# Schematic.net
KiCad netlist of a schematic drawn in Altium Designer
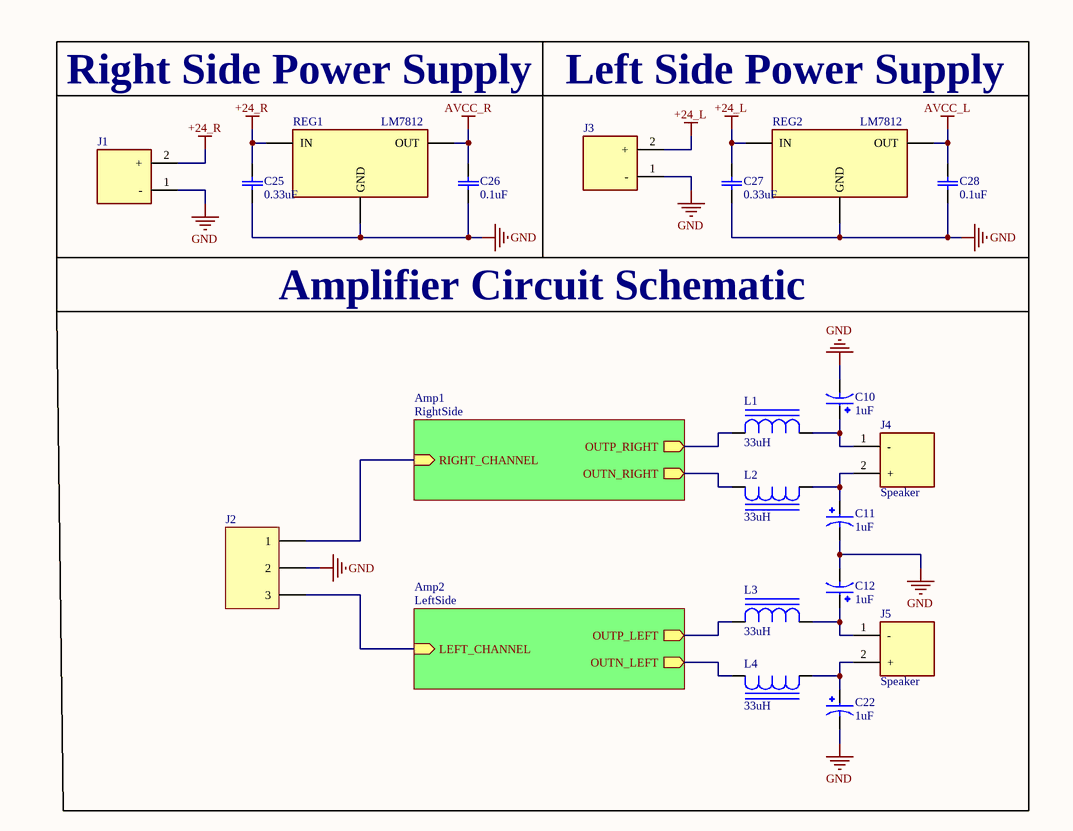
[diagram p0: Schematic.SchDoc]

(export (version "E")
  (design (tool "Eeschema 10.0.6"))
  (components
    (comp (ref "C10")
      (value "1uF")
      (footprint "CAPRADIAL_16X10")
      (fields
        (field (name "DIGI-KEY_PART_NUMBER") "P13679-ND")
        (field (name "MP") "EEU-EE2W560")
        (field (name "MF") "Panasonic")
      )
      (libsource (lib "AltiumLibrary-Mugetsu") (part "CAP ELETRO/TANT"))
    )
    (comp (ref "C11")
      (value "1uF")
      (footprint "CAPRADIAL_16X10")
      (fields
        (field (name "DIGI-KEY_PART_NUMBER") "P13679-ND")
        (field (name "MP") "EEU-EE2W560")
        (field (name "MF") "Panasonic")
      )
      (libsource (lib "") (part "CAP ELETRO/TANT_1"))
    )
    (comp (ref "C12")
      (value "1uF")
      (footprint "CAPRADIAL_16X10")
      (fields
        (field (name "DIGI-KEY_PART_NUMBER") "P13679-ND")
        (field (name "MP") "EEU-EE2W560")
        (field (name "MF") "Panasonic")
      )
      (libsource (lib "AltiumLibrary-Mugetsu") (part "CAP ELETRO/TANT"))
    )
    (comp (ref "C22")
      (value "1uF")
      (footprint "CAPRADIAL_16X10")
      (fields
        (field (name "DIGI-KEY_PART_NUMBER") "P13679-ND")
        (field (name "MP") "EEU-EE2W560")
        (field (name "MF") "Panasonic")
      )
      (libsource (lib "") (part "CAP ELETRO/TANT_1"))
    )
    (comp (ref "C25")
      (value "0.33uF")
      (footprint "CERAMIC0805")
      (fields (field (name "MF") "KEMET") (field (name "MP") "TAJC226M025RNJ"))
      (libsource (lib "AltiumLibrary-Mugetsu") (part "Cap"))
    )
    (comp (ref "C26")
      (value "0.1uF")
      (footprint "CERAMIC0805")
      (fields (field (name "MF") "KEMET") (field (name "MP") "TAJC226M025RNJ"))
      (libsource (lib "AltiumLibrary-Mugetsu") (part "Cap"))
    )
    (comp (ref "C27")
      (value "0.33uF")
      (footprint "CERAMIC0805")
      (fields (field (name "MF") "KEMET") (field (name "MP") "TAJC226M025RNJ"))
      (libsource (lib "AltiumLibrary-Mugetsu") (part "Cap"))
    )
    (comp (ref "C28")
      (value "0.1uF")
      (footprint "CERAMIC0805")
      (fields (field (name "MF") "KEMET") (field (name "MP") "TAJC226M025RNJ"))
      (libsource (lib "AltiumLibrary-Mugetsu") (part "Cap"))
    )
    (comp (ref "J1")
      (value "Borne KF301-2P")
      (footprint "Borne KF301-2P")
      (description "2 Pin Terminal Block 5mm Pitch")
      (fields (field (name "MP") "KF301-2P"))
      (libsource (lib "AltiumLibrary-Mugetsu") (part "Borne KF301-2P"))
    )
    (comp (ref "J2")
      (value "Borne KF301-3P")
      (footprint "Borne KF301-3P")
      (libsource (lib "AltiumLibrary-Mugetsu") (part "Borne KF301-3P"))
    )
    (comp (ref "J3")
      (value "Borne KF301-2P")
      (footprint "Borne KF301-2P")
      (description "2 Pin Terminal Block 5mm Pitch")
      (fields (field (name "MP") "KF301-2P"))
      (libsource (lib "AltiumLibrary-Mugetsu") (part "Borne KF301-2P"))
    )
    (comp (ref "J4")
      (value "Speaker")
      (footprint "Borne KF301-2P")
      (description "2 Pin Terminal Block 5mm Pitch")
      (fields (field (name "MP") "KF301-2P"))
      (libsource (lib "") (part "Borne KF301-2P_1"))
    )
    (comp (ref "J5")
      (value "Speaker")
      (footprint "Borne KF301-2P")
      (description "2 Pin Terminal Block 5mm Pitch")
      (fields (field (name "MP") "KF301-2P"))
      (libsource (lib "") (part "Borne KF301-2P_1"))
    )
    (comp (ref "L1")
      (value "33uH")
      (footprint "DR124")
      (libsource (lib "AltiumLibrary-Mugetsu") (part "Inductor"))
    )
    (comp (ref "L2")
      (value "33uH")
      (footprint "DR124")
      (libsource (lib "AltiumLibrary-Mugetsu") (part "Inductor"))
    )
    (comp (ref "L3")
      (value "33uH")
      (footprint "DR124")
      (libsource (lib "AltiumLibrary-Mugetsu") (part "Inductor"))
    )
    (comp (ref "L4")
      (value "33uH")
      (footprint "DR124")
      (libsource (lib "AltiumLibrary-Mugetsu") (part "Inductor"))
    )
    (comp (ref "REG1")
      (value "LM7812")
      (footprint "TO-220-3")
      (description "Regulador de tensão linha LM78XX")
      (fields (field (name "MP") "LM7805S/NOPB") (field (name "MF") "Texas Instruments"))
      (libsource (lib "AltiumLibrary-Mugetsu") (part "LM78XX"))
    )
    (comp (ref "REG2")
      (value "LM7812")
      (footprint "TO-220-3")
      (description "Regulador de tensão linha LM78XX")
      (fields (field (name "MP") "LM7805S/NOPB") (field (name "MF") "Texas Instruments"))
      (libsource (lib "AltiumLibrary-Mugetsu") (part "LM78XX"))
    )
  )
  (nets
    (net (code "1") (name "+24_L") (class "Default")
      (node (ref "C27") (pin "2") (pinfunction "C2_2") (pintype "passive"))
      (node (ref "J3") (pin "2") (pinfunction "+_2") (pintype "passive"))
      (node (ref "REG2") (pin "1") (pinfunction "IN_1") (pintype "power_in"))
    )
    (net (code "2") (name "+24_R") (class "Default")
      (node (ref "C25") (pin "2") (pinfunction "C2_2") (pintype "passive"))
      (node (ref "J1") (pin "2") (pinfunction "+_2") (pintype "passive"))
      (node (ref "REG1") (pin "1") (pinfunction "IN_1") (pintype "power_in"))
    )
    (net (code "3") (name "/LEFT_CHANNEL") (class "Default")
      (node (ref "J2") (pin "3") (pinfunction "3_3") (pintype "passive"))
    )
    (net (code "4") (name "/OUTN_LEFT") (class "Default")
      (node (ref "L4") (pin "2") (pinfunction "2_2") (pintype "passive"))
    )
    (net (code "5") (name "/OUTN_RIGHT") (class "Default")
      (node (ref "L2") (pin "2") (pinfunction "2_2") (pintype "passive"))
    )
    (net (code "6") (name "/OUTP_LEFT") (class "Default")
      (node (ref "L3") (pin "1") (pinfunction "1_1") (pintype "passive"))
    )
    (net (code "7") (name "/OUTP_RIGHT") (class "Default")
      (node (ref "L1") (pin "1") (pinfunction "1_1") (pintype "passive"))
    )
    (net (code "8") (name "/RIGHT_CHANNEL") (class "Default")
      (node (ref "J2") (pin "1") (pinfunction "1_1") (pintype "passive"))
    )
    (net (code "9") (name "AVCC_L") (class "Default")
      (node (ref "C28") (pin "2") (pinfunction "C2_2") (pintype "passive"))
      (node (ref "REG2") (pin "3") (pinfunction "OUT_3") (pintype "power_in"))
    )
    (net (code "10") (name "AVCC_R") (class "Default")
      (node (ref "C26") (pin "2") (pinfunction "C2_2") (pintype "passive"))
      (node (ref "REG1") (pin "3") (pinfunction "OUT_3") (pintype "power_in"))
    )
    (net (code "11") (name "GND") (class "Default")
      (node (ref "C10") (pin "N") (pinfunction "N_N") (pintype "passive"))
      (node (ref "C11") (pin "N") (pinfunction "N_N") (pintype "passive"))
      (node (ref "C12") (pin "N") (pinfunction "N_N") (pintype "passive"))
      (node (ref "C22") (pin "N") (pinfunction "N_N") (pintype "passive"))
      (node (ref "C25") (pin "1") (pinfunction "C1_1") (pintype "passive"))
      (node (ref "C26") (pin "1") (pinfunction "C1_1") (pintype "passive"))
      (node (ref "C27") (pin "1") (pinfunction "C1_1") (pintype "passive"))
      (node (ref "C28") (pin "1") (pinfunction "C1_1") (pintype "passive"))
      (node (ref "J1") (pin "1") (pinfunction "-_1") (pintype "passive"))
      (node (ref "J2") (pin "2") (pinfunction "2_2") (pintype "passive"))
      (node (ref "J3") (pin "1") (pinfunction "-_1") (pintype "passive"))
      (node (ref "REG1") (pin "2") (pinfunction "GND_2") (pintype "power_in"))
      (node (ref "REG2") (pin "2") (pinfunction "GND_2") (pintype "power_in"))
    )
    (net (code "12") (name "Net-(J4-+)") (class "Default")
      (node (ref "C11") (pin "P") (pinfunction "P_P") (pintype "passive"))
      (node (ref "J4") (pin "2") (pinfunction "+_2") (pintype "passive"))
      (node (ref "L2") (pin "1") (pinfunction "1_1") (pintype "passive"))
    )
    (net (code "13") (name "Net-(J4--)") (class "Default")
      (node (ref "C10") (pin "P") (pinfunction "P_P") (pintype "passive"))
      (node (ref "J4") (pin "1") (pinfunction "-_1") (pintype "passive"))
      (node (ref "L1") (pin "2") (pinfunction "2_2") (pintype "passive"))
    )
    (net (code "14") (name "Net-(J5-+)") (class "Default")
      (node (ref "C22") (pin "P") (pinfunction "P_P") (pintype "passive"))
      (node (ref "J5") (pin "2") (pinfunction "+_2") (pintype "passive"))
      (node (ref "L4") (pin "1") (pinfunction "1_1") (pintype "passive"))
    )
    (net (code "15") (name "Net-(J5--)") (class "Default")
      (node (ref "C12") (pin "P") (pinfunction "P_P") (pintype "passive"))
      (node (ref "J5") (pin "1") (pinfunction "-_1") (pintype "passive"))
      (node (ref "L3") (pin "2") (pinfunction "2_2") (pintype "passive"))
    )
  )
)
